# Cross-Analog.net
KiCad netlist of a schematic drawn in Altium Designer
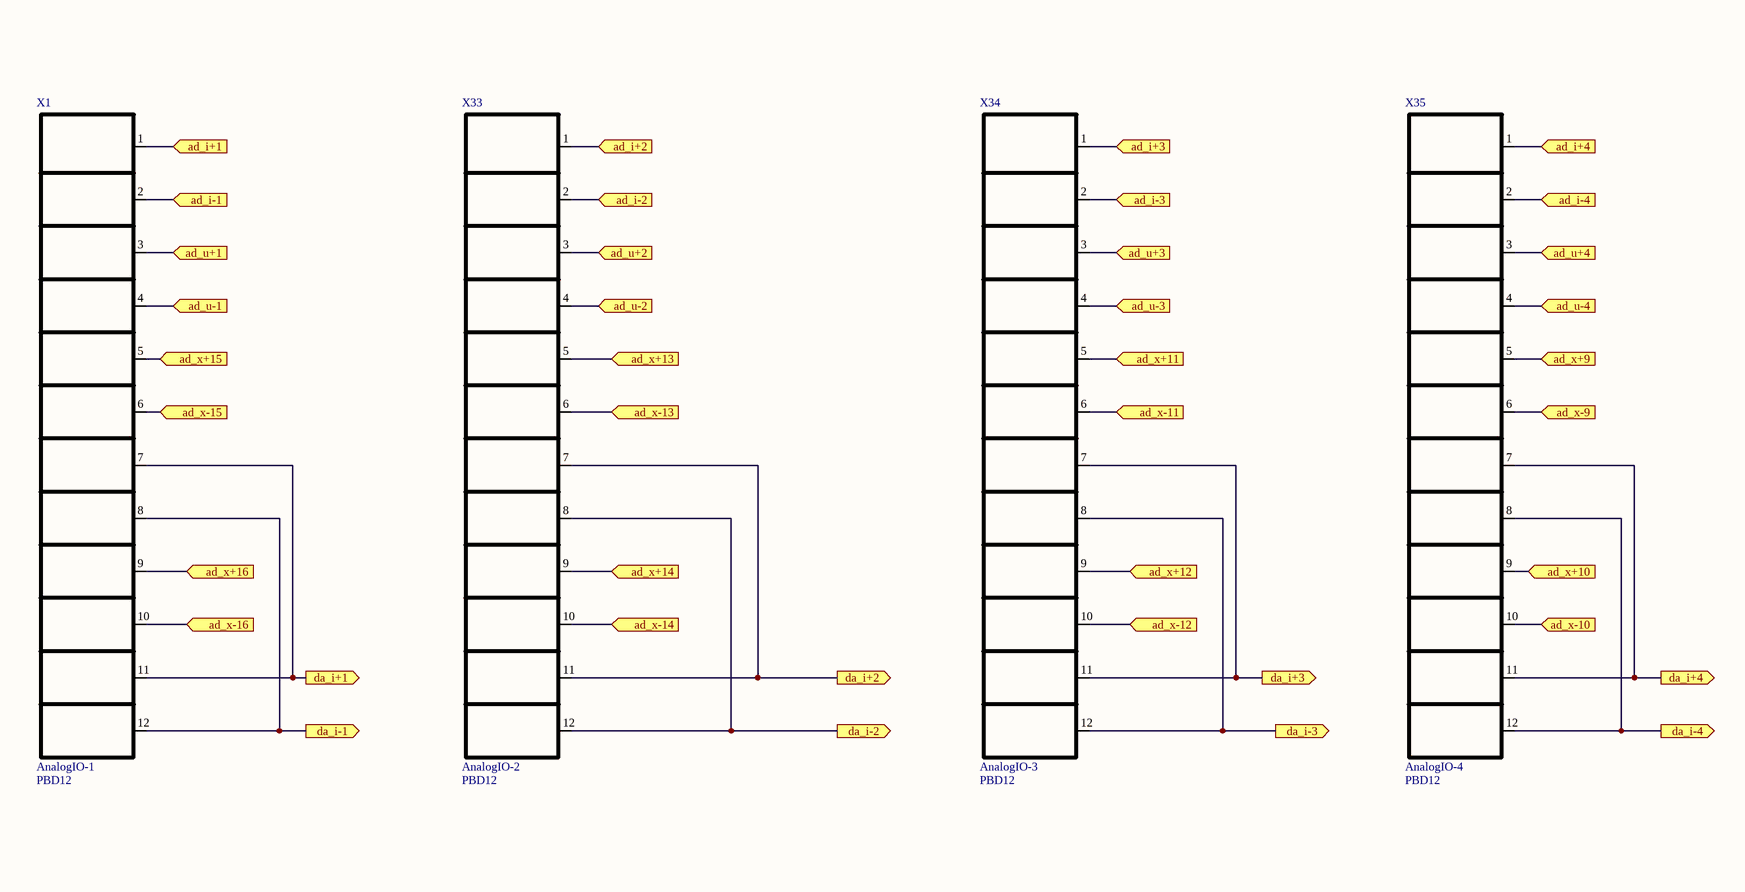
[diagram p0: Cross-Analog.SchDoc, left]
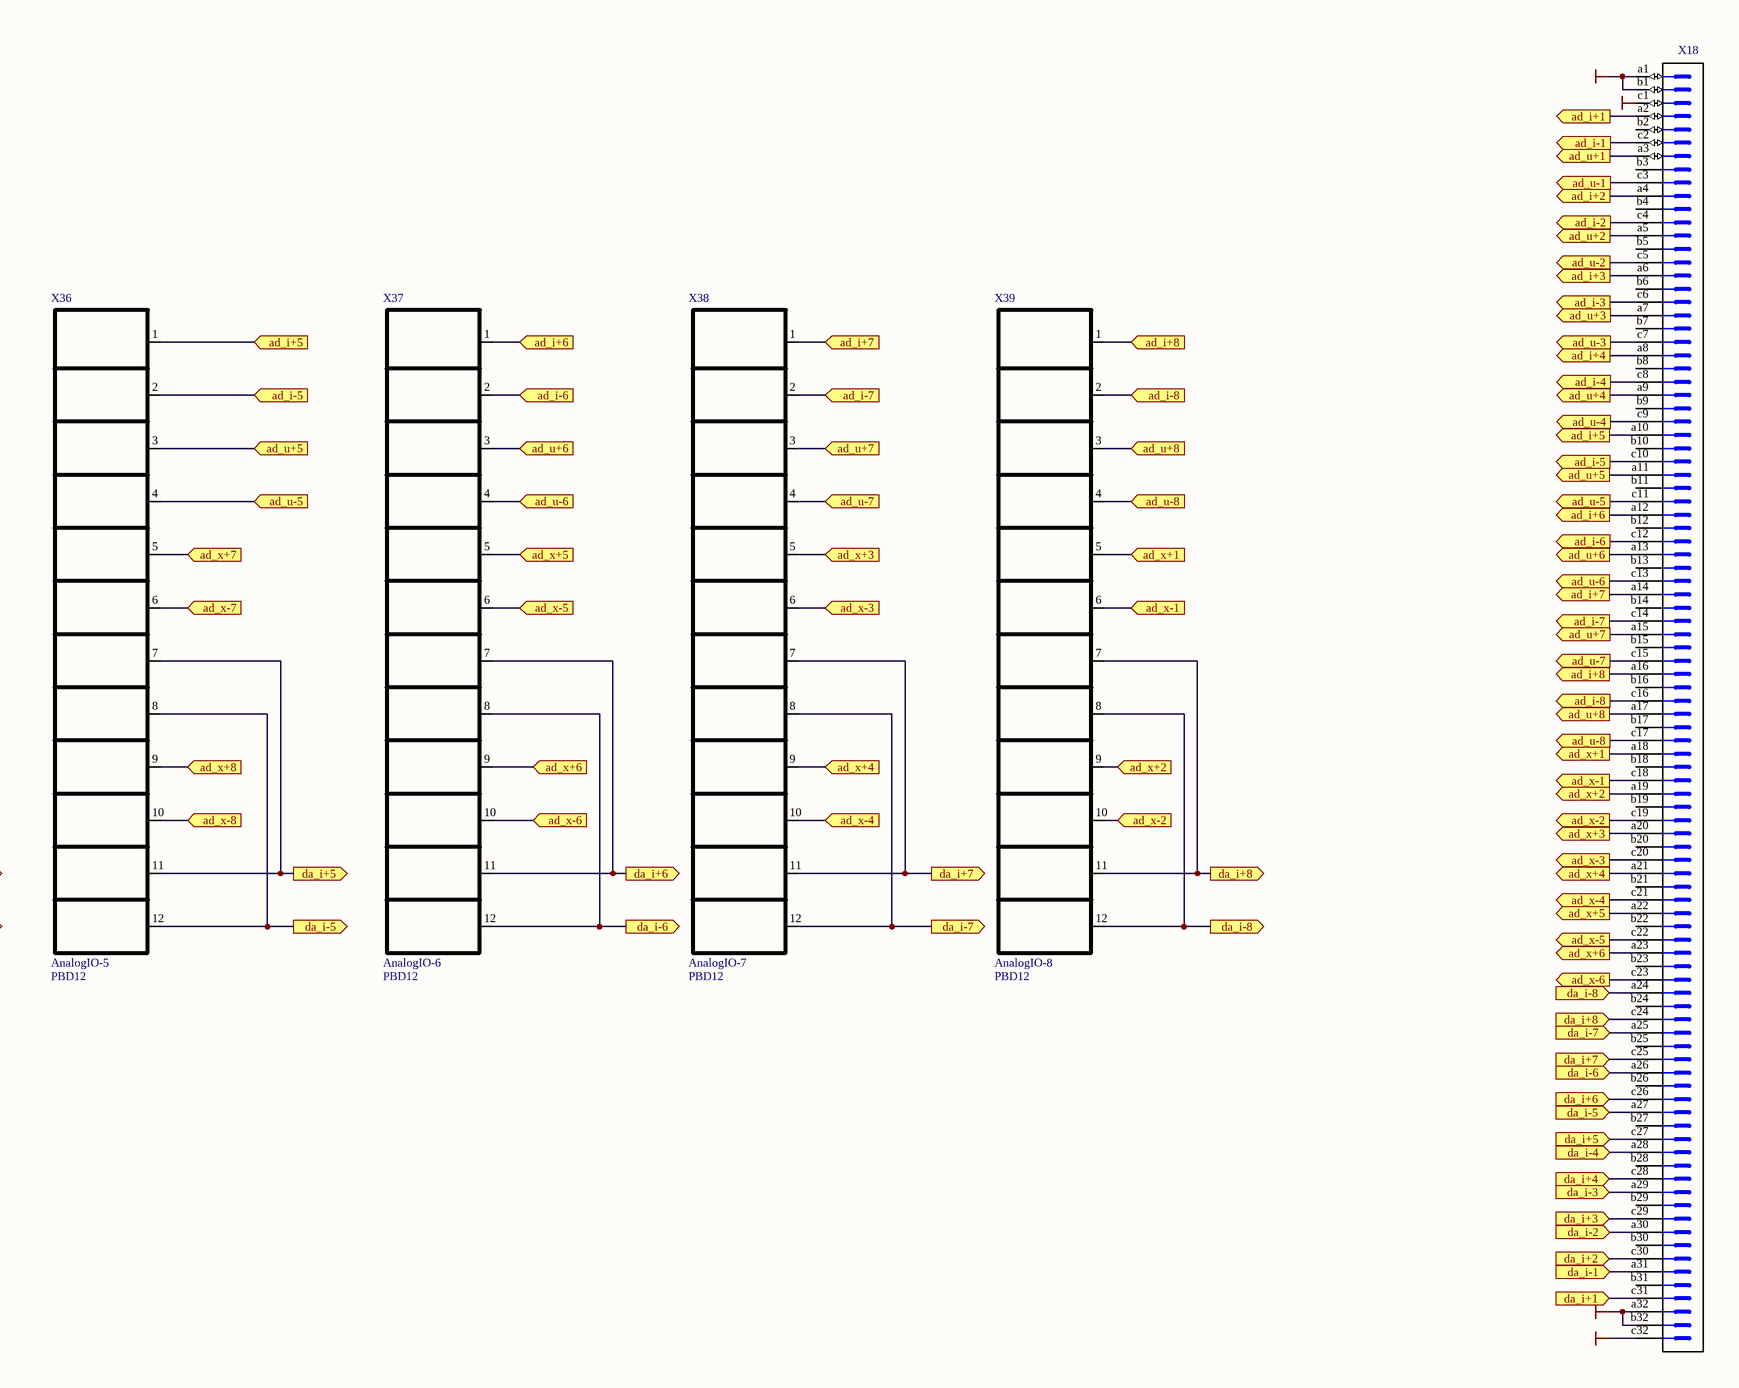
[diagram p1: Cross-Analog.SchDoc, right]

(export (version "E")
  (design (tool "Eeschema 10.0.6"))
  (components
    (comp (ref "X1")
      (value "AnalogIO-1")
      (footprint "DIP_12-254_F")
      (description "12 pin TRH connector 2.54mm pitch")
      (fields (field (name "DEVICE") "PBD12"))
      (libsource (lib "L1") (part "PBD12"))
    )
    (comp (ref "X18")
      (value "HARTING_09 03 196 6921")
      (footprint "HARTING_09 03 196 6921")
      (description "Connector 96 Male Right Angle")
      (libsource (lib "L1") (part "HARTING_09 03 196 6921"))
    )
    (comp (ref "X33")
      (value "AnalogIO-2")
      (footprint "DIP_12-254_F")
      (description "12 pin TRH connector 2.54mm pitch")
      (fields (field (name "DEVICE") "PBD12"))
      (libsource (lib "L1") (part "PBD12"))
    )
    (comp (ref "X34")
      (value "AnalogIO-3")
      (footprint "DIP_12-254_F")
      (description "12 pin TRH connector 2.54mm pitch")
      (fields (field (name "DEVICE") "PBD12"))
      (libsource (lib "L1") (part "PBD12"))
    )
    (comp (ref "X35")
      (value "AnalogIO-4")
      (footprint "DIP_12-254_F")
      (description "12 pin TRH connector 2.54mm pitch")
      (fields (field (name "DEVICE") "PBD12"))
      (libsource (lib "L1") (part "PBD12"))
    )
    (comp (ref "X36")
      (value "AnalogIO-5")
      (footprint "DIP_12-254_F")
      (description "12 pin TRH connector 2.54mm pitch")
      (fields (field (name "DEVICE") "PBD12"))
      (libsource (lib "L1") (part "PBD12"))
    )
    (comp (ref "X37")
      (value "AnalogIO-6")
      (footprint "DIP_12-254_F")
      (description "12 pin TRH connector 2.54mm pitch")
      (fields (field (name "DEVICE") "PBD12"))
      (libsource (lib "L1") (part "PBD12"))
    )
    (comp (ref "X38")
      (value "AnalogIO-7")
      (footprint "DIP_12-254_F")
      (description "12 pin TRH connector 2.54mm pitch")
      (fields (field (name "DEVICE") "PBD12"))
      (libsource (lib "L1") (part "PBD12"))
    )
    (comp (ref "X39")
      (value "AnalogIO-8")
      (footprint "DIP_12-254_F")
      (description "12 pin TRH connector 2.54mm pitch")
      (fields (field (name "DEVICE") "PBD12"))
      (libsource (lib "L1") (part "PBD12"))
    )
  )
  (nets
    (net (code "1") (name "/ad_i+1") (class "Default")
      (node (ref "X1") (pin "1") (pinfunction "1_1") (pintype "passive"))
      (node (ref "X18") (pin "a2") (pinfunction "a2_a2") (pintype "bidirectional"))
    )
    (net (code "2") (name "/ad_i+2") (class "Default")
      (node (ref "X18") (pin "a4") (pinfunction "a4_a4") (pintype "power_in"))
      (node (ref "X33") (pin "1") (pinfunction "1_1") (pintype "passive"))
    )
    (net (code "3") (name "/ad_i+3") (class "Default")
      (node (ref "X18") (pin "a6") (pinfunction "a6_a6") (pintype "power_in"))
      (node (ref "X34") (pin "1") (pinfunction "1_1") (pintype "passive"))
    )
    (net (code "4") (name "/ad_i+4") (class "Default")
      (node (ref "X18") (pin "a8") (pinfunction "a8_a8") (pintype "power_in"))
      (node (ref "X35") (pin "1") (pinfunction "1_1") (pintype "passive"))
    )
    (net (code "5") (name "/ad_i+5") (class "Default")
      (node (ref "X18") (pin "a10") (pinfunction "a10_a10") (pintype "power_in"))
      (node (ref "X36") (pin "1") (pinfunction "1_1") (pintype "passive"))
    )
    (net (code "6") (name "/ad_i+6") (class "Default")
      (node (ref "X18") (pin "a12") (pinfunction "a12_a12") (pintype "power_in"))
      (node (ref "X37") (pin "1") (pinfunction "1_1") (pintype "passive"))
    )
    (net (code "7") (name "/ad_i+7") (class "Default")
      (node (ref "X18") (pin "a14") (pinfunction "a14_a14") (pintype "power_in"))
      (node (ref "X38") (pin "1") (pinfunction "1_1") (pintype "passive"))
    )
    (net (code "8") (name "/ad_i+8") (class "Default")
      (node (ref "X18") (pin "a16") (pinfunction "a16_a16") (pintype "power_in"))
      (node (ref "X39") (pin "1") (pinfunction "1_1") (pintype "passive"))
    )
    (net (code "9") (name "/ad_i-1") (class "Default")
      (node (ref "X1") (pin "2") (pinfunction "2_2") (pintype "passive"))
      (node (ref "X18") (pin "c2") (pinfunction "c2_c2") (pintype "bidirectional"))
    )
    (net (code "10") (name "/ad_i-2") (class "Default")
      (node (ref "X18") (pin "c4") (pinfunction "c4_c4") (pintype "power_in"))
      (node (ref "X33") (pin "2") (pinfunction "2_2") (pintype "passive"))
    )
    (net (code "11") (name "/ad_i-3") (class "Default")
      (node (ref "X18") (pin "c6") (pinfunction "c6_c6") (pintype "power_in"))
      (node (ref "X34") (pin "2") (pinfunction "2_2") (pintype "passive"))
    )
    (net (code "12") (name "/ad_i-4") (class "Default")
      (node (ref "X18") (pin "c8") (pinfunction "c8_c8") (pintype "power_in"))
      (node (ref "X35") (pin "2") (pinfunction "2_2") (pintype "passive"))
    )
    (net (code "13") (name "/ad_i-5") (class "Default")
      (node (ref "X18") (pin "c10") (pinfunction "c10_c10") (pintype "power_in"))
      (node (ref "X36") (pin "2") (pinfunction "2_2") (pintype "passive"))
    )
    (net (code "14") (name "/ad_i-6") (class "Default")
      (node (ref "X18") (pin "c12") (pinfunction "c12_c12") (pintype "power_in"))
      (node (ref "X37") (pin "2") (pinfunction "2_2") (pintype "passive"))
    )
    (net (code "15") (name "/ad_i-7") (class "Default")
      (node (ref "X18") (pin "c14") (pinfunction "c14_c14") (pintype "power_in"))
      (node (ref "X38") (pin "2") (pinfunction "2_2") (pintype "passive"))
    )
    (net (code "16") (name "/ad_i-8") (class "Default")
      (node (ref "X18") (pin "c16") (pinfunction "c16_c16") (pintype "power_in"))
      (node (ref "X39") (pin "2") (pinfunction "2_2") (pintype "passive"))
    )
    (net (code "17") (name "/ad_u+1") (class "Default")
      (node (ref "X1") (pin "3") (pinfunction "3_3") (pintype "passive"))
      (node (ref "X18") (pin "a3") (pinfunction "a3_a3") (pintype "bidirectional"))
    )
    (net (code "18") (name "/ad_u+2") (class "Default")
      (node (ref "X18") (pin "a5") (pinfunction "a5_a5") (pintype "power_in"))
      (node (ref "X33") (pin "3") (pinfunction "3_3") (pintype "passive"))
    )
    (net (code "19") (name "/ad_u+3") (class "Default")
      (node (ref "X18") (pin "a7") (pinfunction "a7_a7") (pintype "power_in"))
      (node (ref "X34") (pin "3") (pinfunction "3_3") (pintype "passive"))
    )
    (net (code "20") (name "/ad_u+4") (class "Default")
      (node (ref "X18") (pin "a9") (pinfunction "a9_a9") (pintype "power_in"))
      (node (ref "X35") (pin "3") (pinfunction "3_3") (pintype "passive"))
    )
    (net (code "21") (name "/ad_u+5") (class "Default")
      (node (ref "X18") (pin "a11") (pinfunction "a11_a11") (pintype "power_in"))
      (node (ref "X36") (pin "3") (pinfunction "3_3") (pintype "passive"))
    )
    (net (code "22") (name "/ad_u+6") (class "Default")
      (node (ref "X18") (pin "a13") (pinfunction "a13_a13") (pintype "power_in"))
      (node (ref "X37") (pin "3") (pinfunction "3_3") (pintype "passive"))
    )
    (net (code "23") (name "/ad_u+7") (class "Default")
      (node (ref "X18") (pin "a15") (pinfunction "a15_a15") (pintype "power_in"))
      (node (ref "X38") (pin "3") (pinfunction "3_3") (pintype "passive"))
    )
    (net (code "24") (name "/ad_u+8") (class "Default")
      (node (ref "X18") (pin "a17") (pinfunction "a17_a17") (pintype "power_in"))
      (node (ref "X39") (pin "3") (pinfunction "3_3") (pintype "passive"))
    )
    (net (code "25") (name "/ad_u-1") (class "Default")
      (node (ref "X1") (pin "4") (pinfunction "4_4") (pintype "passive"))
      (node (ref "X18") (pin "c3") (pinfunction "c3_c3") (pintype "power_in"))
    )
    (net (code "26") (name "/ad_u-2") (class "Default")
      (node (ref "X18") (pin "c5") (pinfunction "c5_c5") (pintype "power_in"))
      (node (ref "X33") (pin "4") (pinfunction "4_4") (pintype "passive"))
    )
    (net (code "27") (name "/ad_u-3") (class "Default")
      (node (ref "X18") (pin "c7") (pinfunction "c7_c7") (pintype "power_in"))
      (node (ref "X34") (pin "4") (pinfunction "4_4") (pintype "passive"))
    )
    (net (code "28") (name "/ad_u-4") (class "Default")
      (node (ref "X18") (pin "c9") (pinfunction "c9_c9") (pintype "power_in"))
      (node (ref "X35") (pin "4") (pinfunction "4_4") (pintype "passive"))
    )
    (net (code "29") (name "/ad_u-5") (class "Default")
      (node (ref "X18") (pin "c11") (pinfunction "c11_c11") (pintype "power_in"))
      (node (ref "X36") (pin "4") (pinfunction "4_4") (pintype "passive"))
    )
    (net (code "30") (name "/ad_u-6") (class "Default")
      (node (ref "X18") (pin "c13") (pinfunction "c13_c13") (pintype "power_in"))
      (node (ref "X37") (pin "4") (pinfunction "4_4") (pintype "passive"))
    )
    (net (code "31") (name "/ad_u-7") (class "Default")
      (node (ref "X18") (pin "c15") (pinfunction "c15_c15") (pintype "power_in"))
      (node (ref "X38") (pin "4") (pinfunction "4_4") (pintype "passive"))
    )
    (net (code "32") (name "/ad_u-8") (class "Default")
      (node (ref "X18") (pin "c17") (pinfunction "c17_c17") (pintype "power_in"))
      (node (ref "X39") (pin "4") (pinfunction "4_4") (pintype "passive"))
    )
    (net (code "33") (name "/ad_x+1") (class "Default")
      (node (ref "X18") (pin "a18") (pinfunction "a18_a18") (pintype "power_in"))
      (node (ref "X39") (pin "5") (pinfunction "5_5") (pintype "passive"))
    )
    (net (code "34") (name "/ad_x+2") (class "Default")
      (node (ref "X18") (pin "a19") (pinfunction "a19_a19") (pintype "power_in"))
      (node (ref "X39") (pin "9") (pinfunction "9_9") (pintype "passive"))
    )
    (net (code "35") (name "/ad_x+3") (class "Default")
      (node (ref "X18") (pin "a20") (pinfunction "a20_a20") (pintype "power_in"))
      (node (ref "X38") (pin "5") (pinfunction "5_5") (pintype "passive"))
    )
    (net (code "36") (name "/ad_x+4") (class "Default")
      (node (ref "X18") (pin "a21") (pinfunction "a21_a21") (pintype "power_in"))
      (node (ref "X38") (pin "9") (pinfunction "9_9") (pintype "passive"))
    )
    (net (code "37") (name "/ad_x+5") (class "Default")
      (node (ref "X18") (pin "a22") (pinfunction "a22_a22") (pintype "power_in"))
      (node (ref "X37") (pin "5") (pinfunction "5_5") (pintype "passive"))
    )
    (net (code "38") (name "/ad_x+6") (class "Default")
      (node (ref "X18") (pin "a23") (pinfunction "a23_a23") (pintype "power_in"))
      (node (ref "X37") (pin "9") (pinfunction "9_9") (pintype "passive"))
    )
    (net (code "39") (name "/ad_x+7") (class "Default")
      (node (ref "X36") (pin "5") (pinfunction "5_5") (pintype "passive"))
    )
    (net (code "40") (name "/ad_x+8") (class "Default")
      (node (ref "X36") (pin "9") (pinfunction "9_9") (pintype "passive"))
    )
    (net (code "41") (name "/ad_x+9") (class "Default")
      (node (ref "X35") (pin "5") (pinfunction "5_5") (pintype "passive"))
    )
    (net (code "42") (name "/ad_x+10") (class "Default")
      (node (ref "X35") (pin "9") (pinfunction "9_9") (pintype "passive"))
    )
    (net (code "43") (name "/ad_x+11") (class "Default")
      (node (ref "X34") (pin "5") (pinfunction "5_5") (pintype "passive"))
    )
    (net (code "44") (name "/ad_x+12") (class "Default")
      (node (ref "X34") (pin "9") (pinfunction "9_9") (pintype "passive"))
    )
    (net (code "45") (name "/ad_x+13") (class "Default")
      (node (ref "X33") (pin "5") (pinfunction "5_5") (pintype "passive"))
    )
    (net (code "46") (name "/ad_x+14") (class "Default")
      (node (ref "X33") (pin "9") (pinfunction "9_9") (pintype "passive"))
    )
    (net (code "47") (name "/ad_x+15") (class "Default")
      (node (ref "X1") (pin "5") (pinfunction "5_5") (pintype "passive"))
    )
    (net (code "48") (name "/ad_x+16") (class "Default")
      (node (ref "X1") (pin "9") (pinfunction "9_9") (pintype "passive"))
    )
    (net (code "49") (name "/ad_x-1") (class "Default")
      (node (ref "X18") (pin "c18") (pinfunction "c18_c18") (pintype "power_in"))
      (node (ref "X39") (pin "6") (pinfunction "6_6") (pintype "passive"))
    )
    (net (code "50") (name "/ad_x-2") (class "Default")
      (node (ref "X18") (pin "c19") (pinfunction "c19_c19") (pintype "power_in"))
      (node (ref "X39") (pin "10") (pinfunction "10_10") (pintype "passive"))
    )
    (net (code "51") (name "/ad_x-3") (class "Default")
      (node (ref "X18") (pin "c20") (pinfunction "c20_c20") (pintype "power_in"))
      (node (ref "X38") (pin "6") (pinfunction "6_6") (pintype "passive"))
    )
    (net (code "52") (name "/ad_x-4") (class "Default")
      (node (ref "X18") (pin "c21") (pinfunction "c21_c21") (pintype "power_in"))
      (node (ref "X38") (pin "10") (pinfunction "10_10") (pintype "passive"))
    )
    (net (code "53") (name "/ad_x-5") (class "Default")
      (node (ref "X18") (pin "c22") (pinfunction "c22_c22") (pintype "power_in"))
      (node (ref "X37") (pin "6") (pinfunction "6_6") (pintype "passive"))
    )
    (net (code "54") (name "/ad_x-6") (class "Default")
      (node (ref "X18") (pin "c23") (pinfunction "c23_c23") (pintype "power_in"))
      (node (ref "X37") (pin "10") (pinfunction "10_10") (pintype "passive"))
    )
    (net (code "55") (name "/ad_x-7") (class "Default")
      (node (ref "X36") (pin "6") (pinfunction "6_6") (pintype "passive"))
    )
    (net (code "56") (name "/ad_x-8") (class "Default")
      (node (ref "X36") (pin "10") (pinfunction "10_10") (pintype "passive"))
    )
    (net (code "57") (name "/ad_x-9") (class "Default")
      (node (ref "X35") (pin "6") (pinfunction "6_6") (pintype "passive"))
    )
    (net (code "58") (name "/ad_x-10") (class "Default")
      (node (ref "X35") (pin "10") (pinfunction "10_10") (pintype "passive"))
    )
    (net (code "59") (name "/ad_x-11") (class "Default")
      (node (ref "X34") (pin "6") (pinfunction "6_6") (pintype "passive"))
    )
    (net (code "60") (name "/ad_x-12") (class "Default")
      (node (ref "X34") (pin "10") (pinfunction "10_10") (pintype "passive"))
    )
    (net (code "61") (name "/ad_x-13") (class "Default")
      (node (ref "X33") (pin "6") (pinfunction "6_6") (pintype "passive"))
    )
    (net (code "62") (name "/ad_x-14") (class "Default")
      (node (ref "X33") (pin "10") (pinfunction "10_10") (pintype "passive"))
    )
    (net (code "63") (name "/ad_x-15") (class "Default")
      (node (ref "X1") (pin "6") (pinfunction "6_6") (pintype "passive"))
    )
    (net (code "64") (name "/ad_x-16") (class "Default")
      (node (ref "X1") (pin "10") (pinfunction "10_10") (pintype "passive"))
    )
    (net (code "65") (name "/da_i+1") (class "Default")
      (node (ref "X1") (pin "11") (pinfunction "11_11") (pintype "passive"))
      (node (ref "X1") (pin "7") (pinfunction "7_7") (pintype "passive"))
      (node (ref "X18") (pin "c31") (pinfunction "c31_c31") (pintype "power_in"))
    )
    (net (code "66") (name "/da_i+2") (class "Default")
      (node (ref "X18") (pin "c30") (pinfunction "c30_c30") (pintype "power_in"))
      (node (ref "X33") (pin "11") (pinfunction "11_11") (pintype "passive"))
      (node (ref "X33") (pin "7") (pinfunction "7_7") (pintype "passive"))
    )
    (net (code "67") (name "/da_i+3") (class "Default")
      (node (ref "X18") (pin "c29") (pinfunction "c29_c29") (pintype "power_in"))
      (node (ref "X34") (pin "11") (pinfunction "11_11") (pintype "passive"))
      (node (ref "X34") (pin "7") (pinfunction "7_7") (pintype "passive"))
    )
    (net (code "68") (name "/da_i+4") (class "Default")
      (node (ref "X18") (pin "c28") (pinfunction "c28_c28") (pintype "power_in"))
      (node (ref "X35") (pin "11") (pinfunction "11_11") (pintype "passive"))
      (node (ref "X35") (pin "7") (pinfunction "7_7") (pintype "passive"))
    )
    (net (code "69") (name "/da_i+5") (class "Default")
      (node (ref "X18") (pin "c27") (pinfunction "c27_c27") (pintype "power_in"))
      (node (ref "X36") (pin "11") (pinfunction "11_11") (pintype "passive"))
      (node (ref "X36") (pin "7") (pinfunction "7_7") (pintype "passive"))
    )
    (net (code "70") (name "/da_i+6") (class "Default")
      (node (ref "X18") (pin "c26") (pinfunction "c26_c26") (pintype "power_in"))
      (node (ref "X37") (pin "11") (pinfunction "11_11") (pintype "passive"))
      (node (ref "X37") (pin "7") (pinfunction "7_7") (pintype "passive"))
    )
    (net (code "71") (name "/da_i+7") (class "Default")
      (node (ref "X18") (pin "c25") (pinfunction "c25_c25") (pintype "power_in"))
      (node (ref "X38") (pin "11") (pinfunction "11_11") (pintype "passive"))
      (node (ref "X38") (pin "7") (pinfunction "7_7") (pintype "passive"))
    )
    (net (code "72") (name "/da_i+8") (class "Default")
      (node (ref "X18") (pin "c24") (pinfunction "c24_c24") (pintype "power_in"))
      (node (ref "X39") (pin "11") (pinfunction "11_11") (pintype "passive"))
      (node (ref "X39") (pin "7") (pinfunction "7_7") (pintype "passive"))
    )
    (net (code "73") (name "/da_i-1") (class "Default")
      (node (ref "X1") (pin "12") (pinfunction "12_12") (pintype "passive"))
      (node (ref "X1") (pin "8") (pinfunction "8_8") (pintype "passive"))
      (node (ref "X18") (pin "a31") (pinfunction "a31_a31") (pintype "power_in"))
    )
    (net (code "74") (name "/da_i-2") (class "Default")
      (node (ref "X18") (pin "a30") (pinfunction "a30_a30") (pintype "power_in"))
      (node (ref "X33") (pin "12") (pinfunction "12_12") (pintype "passive"))
      (node (ref "X33") (pin "8") (pinfunction "8_8") (pintype "passive"))
    )
    (net (code "75") (name "/da_i-3") (class "Default")
      (node (ref "X18") (pin "a29") (pinfunction "a29_a29") (pintype "power_in"))
      (node (ref "X34") (pin "12") (pinfunction "12_12") (pintype "passive"))
      (node (ref "X34") (pin "8") (pinfunction "8_8") (pintype "passive"))
    )
    (net (code "76") (name "/da_i-4") (class "Default")
      (node (ref "X18") (pin "a28") (pinfunction "a28_a28") (pintype "power_in"))
      (node (ref "X35") (pin "12") (pinfunction "12_12") (pintype "passive"))
      (node (ref "X35") (pin "8") (pinfunction "8_8") (pintype "passive"))
    )
    (net (code "77") (name "/da_i-5") (class "Default")
      (node (ref "X18") (pin "a27") (pinfunction "a27_a27") (pintype "power_in"))
      (node (ref "X36") (pin "12") (pinfunction "12_12") (pintype "passive"))
      (node (ref "X36") (pin "8") (pinfunction "8_8") (pintype "passive"))
    )
    (net (code "78") (name "/da_i-6") (class "Default")
      (node (ref "X18") (pin "a26") (pinfunction "a26_a26") (pintype "power_in"))
      (node (ref "X37") (pin "12") (pinfunction "12_12") (pintype "passive"))
      (node (ref "X37") (pin "8") (pinfunction "8_8") (pintype "passive"))
    )
    (net (code "79") (name "/da_i-7") (class "Default")
      (node (ref "X18") (pin "a25") (pinfunction "a25_a25") (pintype "power_in"))
      (node (ref "X38") (pin "12") (pinfunction "12_12") (pintype "passive"))
      (node (ref "X38") (pin "8") (pinfunction "8_8") (pintype "passive"))
    )
    (net (code "80") (name "/da_i-8") (class "Default")
      (node (ref "X18") (pin "a24") (pinfunction "a24_a24") (pintype "power_in"))
      (node (ref "X39") (pin "12") (pinfunction "12_12") (pintype "passive"))
      (node (ref "X39") (pin "8") (pinfunction "8_8") (pintype "passive"))
    )
    (net (code "81") (name "GND") (class "Default")
      (node (ref "X18") (pin "a1") (pinfunction "a1_a1") (pintype "bidirectional"))
      (node (ref "X18") (pin "a32") (pinfunction "a32_a32") (pintype "power_in"))
      (node (ref "X18") (pin "b1") (pinfunction "b1_b1") (pintype "bidirectional"))
      (node (ref "X18") (pin "b32") (pinfunction "b32_b32") (pintype "power_in"))
      (node (ref "X18") (pin "c1") (pinfunction "c1_c1") (pintype "bidirectional"))
      (node (ref "X18") (pin "c32") (pinfunction "c32_c32") (pintype "power_in"))
    )
    (net (code "82") (name "unconnected-(X18-5-Padb2)") (class "Default")
      (node (ref "X18") (pin "b2") (pinfunction "5_b2") (pintype "bidirectional"))
    )
    (net (code "83") (name "unconnected-(X18-Padb3)") (class "Default")
      (node (ref "X18") (pin "b3") (pinfunction "b3_b3") (pintype "power_in"))
    )
    (net (code "84") (name "unconnected-(X18-Padb4)") (class "Default")
      (node (ref "X18") (pin "b4") (pinfunction "b4_b4") (pintype "power_in"))
    )
    (net (code "85") (name "unconnected-(X18-Padb5)") (class "Default")
      (node (ref "X18") (pin "b5") (pinfunction "b5_b5") (pintype "power_in"))
    )
    (net (code "86") (name "unconnected-(X18-Padb6)") (class "Default")
      (node (ref "X18") (pin "b6") (pinfunction "b6_b6") (pintype "power_in"))
    )
    (net (code "87") (name "unconnected-(X18-Padb7)") (class "Default")
      (node (ref "X18") (pin "b7") (pinfunction "b7_b7") (pintype "power_in"))
    )
    (net (code "88") (name "unconnected-(X18-Padb8)") (class "Default")
      (node (ref "X18") (pin "b8") (pinfunction "b8_b8") (pintype "power_in"))
    )
    (net (code "89") (name "unconnected-(X18-Padb9)") (class "Default")
      (node (ref "X18") (pin "b9") (pinfunction "b9_b9") (pintype "power_in"))
    )
    (net (code "90") (name "unconnected-(X18-Padb10)") (class "Default")
      (node (ref "X18") (pin "b10") (pinfunction "b10_b10") (pintype "power_in"))
    )
    (net (code "91") (name "unconnected-(X18-Padb11)") (class "Default")
      (node (ref "X18") (pin "b11") (pinfunction "b11_b11") (pintype "power_in"))
    )
    (net (code "92") (name "unconnected-(X18-Padb12)") (class "Default")
      (node (ref "X18") (pin "b12") (pinfunction "b12_b12") (pintype "power_in"))
    )
    (net (code "93") (name "unconnected-(X18-Padb13)") (class "Default")
      (node (ref "X18") (pin "b13") (pinfunction "b13_b13") (pintype "power_in"))
    )
    (net (code "94") (name "unconnected-(X18-Padb14)") (class "Default")
      (node (ref "X18") (pin "b14") (pinfunction "b14_b14") (pintype "power_in"))
    )
    (net (code "95") (name "unconnected-(X18-Padb15)") (class "Default")
      (node (ref "X18") (pin "b15") (pinfunction "b15_b15") (pintype "power_in"))
    )
    (net (code "96") (name "unconnected-(X18-Padb16)") (class "Default")
      (node (ref "X18") (pin "b16") (pinfunction "b16_b16") (pintype "power_in"))
    )
    (net (code "97") (name "unconnected-(X18-Padb17)") (class "Default")
      (node (ref "X18") (pin "b17") (pinfunction "b17_b17") (pintype "power_in"))
    )
    (net (code "98") (name "unconnected-(X18-Padb18)") (class "Default")
      (node (ref "X18") (pin "b18") (pinfunction "b18_b18") (pintype "power_in"))
    )
    (net (code "99") (name "unconnected-(X18-Padb19)") (class "Default")
      (node (ref "X18") (pin "b19") (pinfunction "b19_b19") (pintype "power_in"))
    )
    (net (code "100") (name "unconnected-(X18-Padb20)") (class "Default")
      (node (ref "X18") (pin "b20") (pinfunction "b20_b20") (pintype "power_in"))
    )
    (net (code "101") (name "unconnected-(X18-Padb21)") (class "Default")
      (node (ref "X18") (pin "b21") (pinfunction "b21_b21") (pintype "power_in"))
    )
    (net (code "102") (name "unconnected-(X18-Padb22)") (class "Default")
      (node (ref "X18") (pin "b22") (pinfunction "b22_b22") (pintype "power_in"))
    )
    (net (code "103") (name "unconnected-(X18-Padb23)") (class "Default")
      (node (ref "X18") (pin "b23") (pinfunction "b23_b23") (pintype "power_in"))
    )
    (net (code "104") (name "unconnected-(X18-Padb24)") (class "Default")
      (node (ref "X18") (pin "b24") (pinfunction "b24_b24") (pintype "power_in"))
    )
    (net (code "105") (name "unconnected-(X18-Padb25)") (class "Default")
      (node (ref "X18") (pin "b25") (pinfunction "b25_b25") (pintype "power_in"))
    )
    (net (code "106") (name "unconnected-(X18-Padb26)") (class "Default")
      (node (ref "X18") (pin "b26") (pinfunction "b26_b26") (pintype "power_in"))
    )
    (net (code "107") (name "unconnected-(X18-Padb27)") (class "Default")
      (node (ref "X18") (pin "b27") (pinfunction "b27_b27") (pintype "power_in"))
    )
    (net (code "108") (name "unconnected-(X18-Padb28)") (class "Default")
      (node (ref "X18") (pin "b28") (pinfunction "b28_b28") (pintype "power_in"))
    )
    (net (code "109") (name "unconnected-(X18-Padb29)") (class "Default")
      (node (ref "X18") (pin "b29") (pinfunction "b29_b29") (pintype "power_in"))
    )
    (net (code "110") (name "unconnected-(X18-Padb30)") (class "Default")
      (node (ref "X18") (pin "b30") (pinfunction "b30_b30") (pintype "power_in"))
    )
    (net (code "111") (name "unconnected-(X18-Padb31)") (class "Default")
      (node (ref "X18") (pin "b31") (pinfunction "b31_b31") (pintype "power_in"))
    )
  )
)
